# H01R0_Frontend.net
KiCad netlist of a schematic drawn in Altium Designer
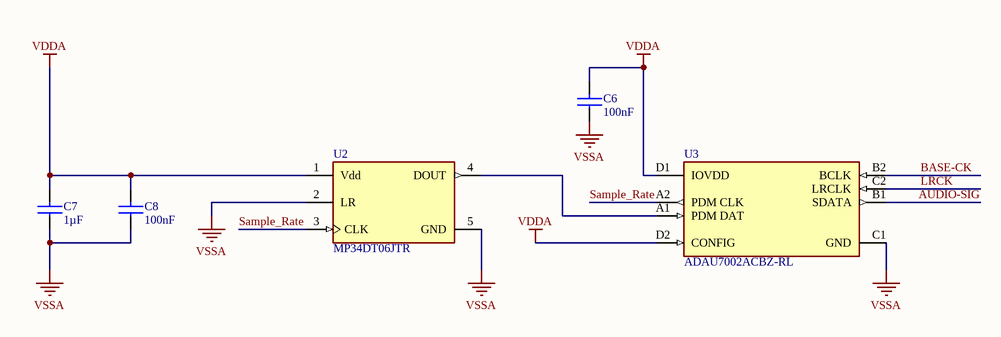
[diagram p0: H01R0_Frontend.SchDoc]

(export (version "E")
  (design (tool "Eeschema 10.0.6"))
  (components
    (comp (ref "C6")
      (value "100nF")
      (footprint "C0603")
      (fields
        (field (name "MANUFACTURER") "Samsung Electro-Mechanics")
        (field (name "MANUFACTURER PART NUMBER") "CL10B104KA8NNNC")
        (field (name "TOLERANCE") "10%")
      )
      (libsource (lib "Hexabitz Altium Library") (part "generic Capacitor"))
    )
    (comp (ref "C7")
      (value "1µF")
      (footprint "C0805")
      (description "Ceramic Capacitor, Ceramic, 16V, 10% +Tol, 10% -Tol, X7R, 15% TC, 1uF, Surface Mount, 0805")
      (fields
        (field (name "MANUFACTURER") "Yageo Group")
        (field (name "MANUFACTURER PART NUMBER") "CC0805KKX7R7BB105")
      )
      (libsource (lib "Hexabitz Altium Library") (part "generic Capacitor"))
    )
    (comp (ref "C8")
      (value "100nF")
      (footprint "C0603")
      (fields
        (field (name "MANUFACTURER") "Samsung Electro-Mechanics")
        (field (name "MANUFACTURER PART NUMBER") "CL10B104KA8NNNC")
        (field (name "TOLERANCE") "10%")
      )
      (libsource (lib "Hexabitz Altium Library") (part "generic Capacitor"))
    )
    (comp (ref "U2")
      (value "MP34DT06JTR")
      (footprint "FP-HCLGA4-DM00231908-MFG")
      (description "MEMS AUDIO SENSOR OMNIDIRECTIONA")
      (fields
        (field (name "MANUFACTURER") "STMicroelectronics")
        (field (name "OCTOPART") "https://octopart.com/mp34dt06jtr-stmicroelectronics-94413825")
      )
      (libsource (lib "Altium Content Vault") (part "1f09fff9aa5ba159ad793fb03c9bd88"))
    )
    (comp (ref "U3")
      (value "ADAU7002ACBZ-RL")
      (footprint "FP-CB-8-6-IPC_B")
      (description "IC SAMPLE RATE CONVERTER 8WLCSP")
      (libsource (lib "Altium Content Vault") (part "733fa76a9435a4818337fa63b2bd65c"))
    )
  )
  (nets
    (net (code "1") (name "/AUDIO-SIG") (class "Default")
      (node (ref "U3") (pin "B1") (pinfunction "SDATA_B1") (pintype "output"))
    )
    (net (code "2") (name "/BASE-CK") (class "Default")
      (node (ref "U3") (pin "B2") (pinfunction "BCLK_B2") (pintype "input"))
    )
    (net (code "3") (name "/LRCK") (class "Default")
      (node (ref "U3") (pin "C2") (pinfunction "LRCLK_C2") (pintype "input"))
    )
    (net (code "4") (name "/Sample_Rate") (class "Default")
      (node (ref "U2") (pin "3") (pinfunction "CLK_3") (pintype "input"))
      (node (ref "U3") (pin "A2") (pinfunction "PDM_CLK_A2") (pintype "output"))
    )
    (net (code "5") (name "Net-(U2-DOUT)") (class "Default")
      (node (ref "U2") (pin "4") (pinfunction "DOUT_4") (pintype "output"))
      (node (ref "U3") (pin "A1") (pinfunction "PDM_DAT_A1") (pintype "input"))
    )
    (net (code "6") (name "VDDA") (class "Default")
      (node (ref "C6") (pin "2") (pinfunction "2_2") (pintype "passive"))
      (node (ref "C7") (pin "2") (pinfunction "2_2") (pintype "passive"))
      (node (ref "C8") (pin "2") (pinfunction "2_2") (pintype "passive"))
      (node (ref "U2") (pin "1") (pinfunction "Vdd_1") (pintype "power_in"))
      (node (ref "U3") (pin "D1") (pinfunction "IOVDD_D1") (pintype "power_in"))
      (node (ref "U3") (pin "D2") (pinfunction "CONFIG_D2") (pintype "input"))
    )
    (net (code "7") (name "VSSA") (class "Default")
      (node (ref "C6") (pin "1") (pinfunction "1_1") (pintype "passive"))
      (node (ref "C7") (pin "1") (pinfunction "1_1") (pintype "passive"))
      (node (ref "C8") (pin "1") (pinfunction "1_1") (pintype "passive"))
      (node (ref "U2") (pin "2") (pinfunction "LR_2") (pintype "passive"))
      (node (ref "U2") (pin "5") (pinfunction "GND_5") (pintype "power_in"))
      (node (ref "U3") (pin "C1") (pinfunction "GND_C1") (pintype "power_in"))
    )
  )
)
